# stripdriver.net
KiCad netlist of a schematic drawn in EasyEDA Pro
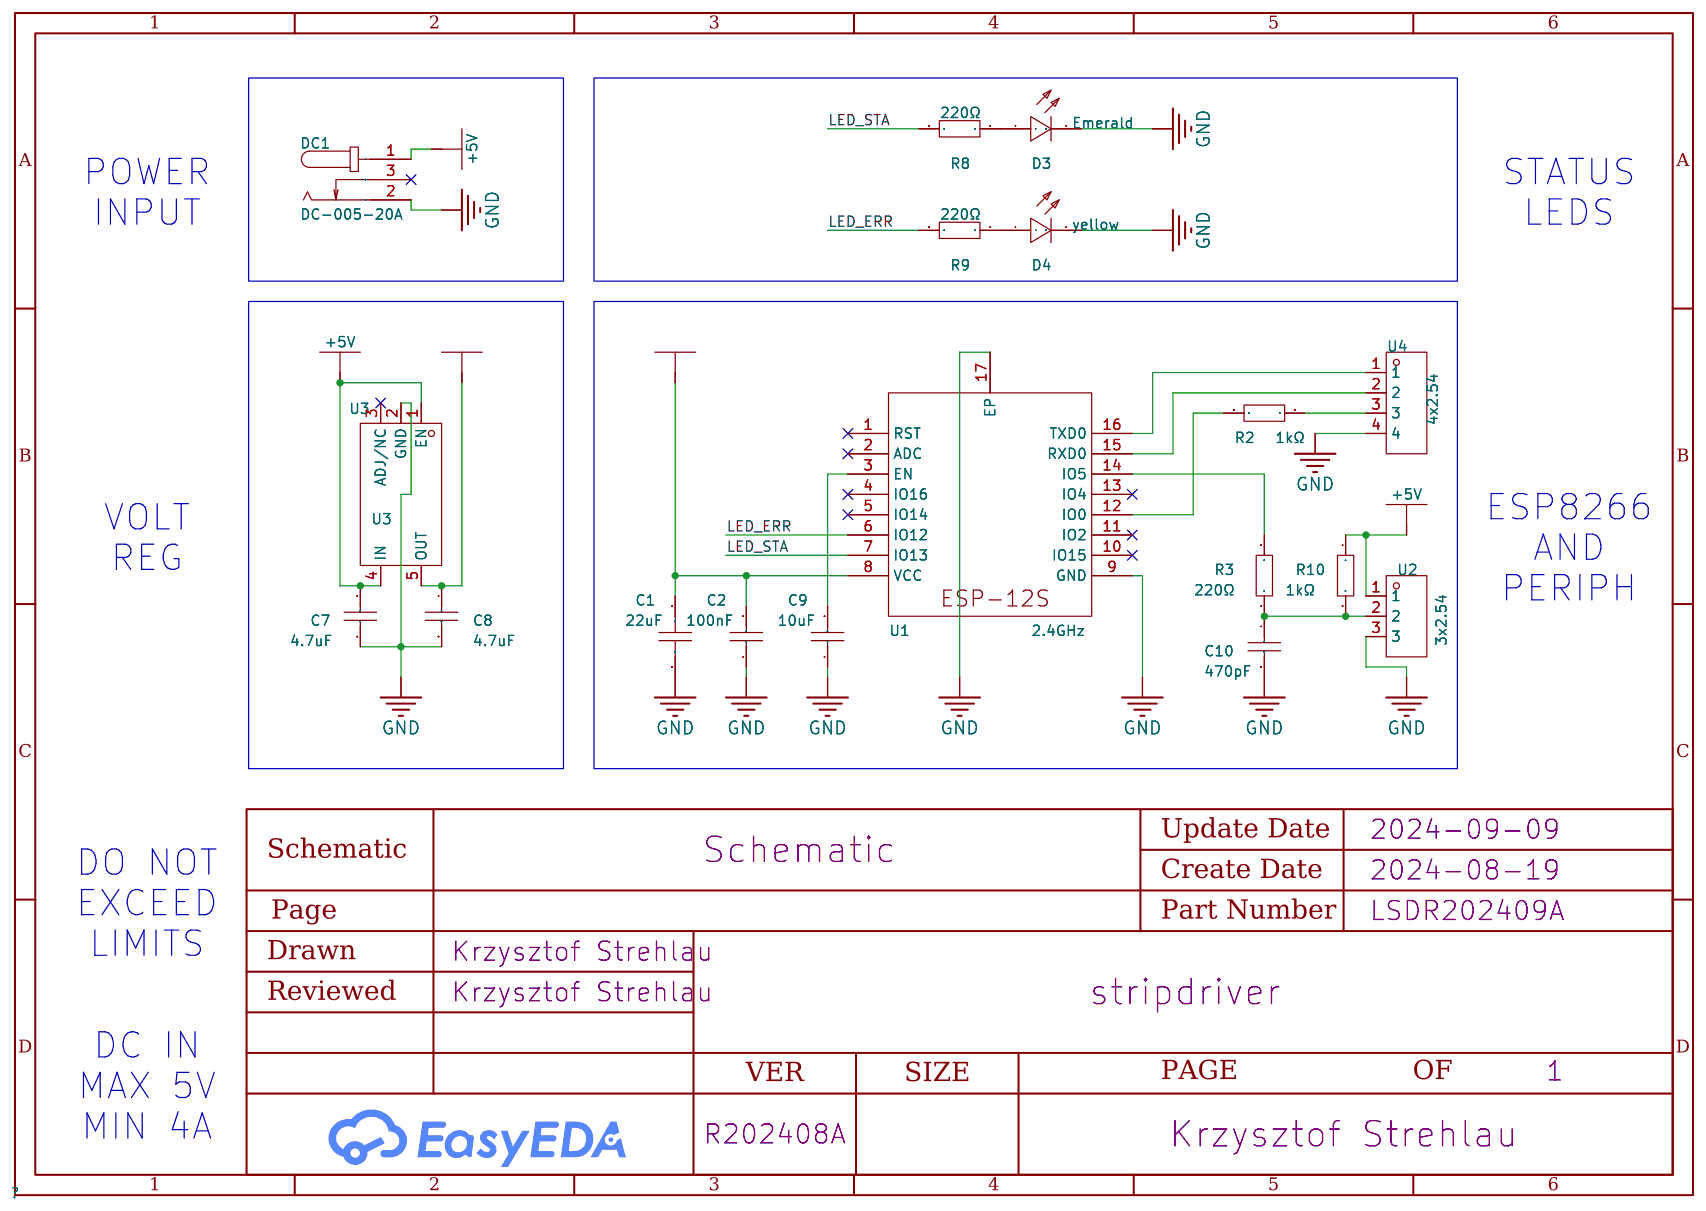
[diagram p0: schematic sheet]

(export (version "E")
  (design (tool "Eeschema 10.0.6"))
  (components
    (comp (ref "C1")
      (value "22uF")
      (footprint "easyedapro:C0805")
      (fields
        (field (name "Manufacturer Part") "CL21A226MAQNNNE")
        (field (name "Manufacturer") "SAMSUNG(三星)")
      )
      (libsource (lib "easyedapro") (part "CL21A226MAQNNNE"))
    )
    (comp (ref "C2")
      (value "100nF")
      (fields
        (field (name "Manufacturer Part") "CC0603KRX7R9BB104")
        (field (name "Manufacturer") "YAGEO(国巨)")
      )
      (libsource (lib "easyedapro") (part "cc0805krx7r9bb104"))
    )
    (comp (ref "C7")
      (value "4.7uF")
      (footprint "easyedapro:C0805")
      (fields
        (field (name "Manufacturer Part") "CL21A475KAQNNNE")
        (field (name "Manufacturer") "SAMSUNG(三星)")
      )
      (libsource (lib "easyedapro") (part "CL21A475KAQNNNE"))
    )
    (comp (ref "C8")
      (value "4.7uF")
      (footprint "easyedapro:C0805")
      (fields
        (field (name "Manufacturer Part") "CL21A475KAQNNNE")
        (field (name "Manufacturer") "SAMSUNG(三星)")
      )
      (libsource (lib "easyedapro") (part "CL21A475KAQNNNE"))
    )
    (comp (ref "C9")
      (value "10uF")
      (footprint "easyedapro:C0805")
      (fields
        (field (name "Manufacturer Part") "CL21A475KAQNNNE")
        (field (name "Manufacturer") "SAMSUNG(三星)")
      )
      (libsource (lib "easyedapro") (part "CL21A475KAQNNNE"))
    )
    (comp (ref "C10")
      (value "470pF")
      (fields
        (field (name "Manufacturer Part") "CC0603KRX7R9BB104")
        (field (name "Manufacturer") "YAGEO(国巨)")
      )
      (libsource (lib "easyedapro") (part "cc0805krx7r9bb104"))
    )
    (comp (ref "D3")
      (value "Emerald")
      (footprint "easyedapro:LED0603-R-RD")
      (fields
        (field (name "Manufacturer Part") "19-217/GHC-YR1S2/3T")
        (field (name "Manufacturer") "EVERLIGHT(亿光)")
      )
      (libsource (lib "easyedapro") (part "19-217/GHC-YR1S2/3T"))
    )
    (comp (ref "D4")
      (value "yellow")
      (footprint "easyedapro:LED0603-R-RD")
      (fields
        (field (name "Manufacturer Part") "19-213/Y2C-CQ2R2L/3T(CY)")
        (field (name "Manufacturer") "EVERLIGHT(亿光)")
      )
      (libsource (lib "easyedapro") (part "19-217/GHC-YR1S2/3T"))
    )
    (comp (ref "DC1")
      (value "DC-005-20A")
      (footprint "easyedapro:DC-IN-TH_DC005")
      (fields (field (name "Manufacturer") "韩国韩荣"))
      (libsource (lib "easyedapro") (part "DC-005-20A"))
    )
    (comp (ref "R2")
      (value "1kΩ")
      (fields (field (name "Manufacturer") "UNI-ROYAL(厚声)"))
      (libsource (lib "easyedapro") (part "0805w8f1052t5e"))
    )
    (comp (ref "R3")
      (value "220Ω")
      (fields (field (name "Manufacturer") "UNI-ROYAL(厚声)"))
      (libsource (lib "easyedapro") (part "0805w8f1052t5e"))
    )
    (comp (ref "R8")
      (value "220Ω")
      (footprint "easyedapro:R0603")
      (fields
        (field (name "Manufacturer Part") "0603WAF2200T5E")
        (field (name "Manufacturer") "UNI-ROYAL(厚声)")
      )
      (libsource (lib "easyedapro") (part "0603WAF2200T5E"))
    )
    (comp (ref "R9")
      (value "220Ω")
      (footprint "easyedapro:R0603")
      (fields
        (field (name "Manufacturer Part") "0603WAF2200T5E")
        (field (name "Manufacturer") "UNI-ROYAL(厚声)")
      )
      (libsource (lib "easyedapro") (part "0603WAF2200T5E"))
    )
    (comp (ref "R10")
      (value "1kΩ")
      (fields (field (name "Manufacturer") "UNI-ROYAL(厚声)"))
      (libsource (lib "easyedapro") (part "0805w8f1052t5e"))
    )
    (comp (ref "U1")
      (value "2.4GHz")
      (footprint "easyedapro:WIRELM-SMD_ESP-12S")
      (fields (field (name "Manufacturer Part") "ESP-12S") (field (name "Manufacturer") "Ai-Thinker(安信可)"))
      (libsource (lib "easyedapro") (part "ESP-12S"))
    )
    (comp (ref "U2")
      (value "3x2.54")
      (footprint "easyedapro:CONN-TH_DB125-2.54-3P-GN")
      (fields
        (field (name "Manufacturer Part") "DB125-2.54-3P-GN-S")
        (field (name "Manufacturer") "DIBO(地博电气)")
      )
      (libsource (lib "easyedapro") (part "DB125-2.54-3P-GN"))
    )
    (comp (ref "U3")
      (value "U3")
      (footprint "easyedapro:SOT-89-5_L4.5-W2.5-P1.50-LS4.5-BR")
      (fields (field (name "Manufacturer Part") "AP7361C-33Y5-13") (field (name "Manufacturer") "DIODES(美台)"))
      (libsource (lib "easyedapro") (part "AP7361C-33Y5-13"))
    )
    (comp (ref "U4")
      (value "4x2.54")
      (footprint "easyedapro:CONN-TH_DB125-2.54-4P-GN")
      (fields (field (name "Manufacturer") "DORABO(地博电气)"))
      (libsource (lib "easyedapro") (part "DB125-2.54-4P-GN"))
    )
  )
  (nets
    (net (code "1") (name "+3.3V") (class "Default")
      (node (ref "C1") (pin "1") (pinfunction "1_1") (pintype "input"))
      (node (ref "C2") (pin "2") (pinfunction "2_2") (pintype "input"))
      (node (ref "C8") (pin "1") (pinfunction "1_1") (pintype "input"))
      (node (ref "U1") (pin "8") (pinfunction "VCC_8") (pintype "unspecified"))
      (node (ref "U3") (pin "5") (pinfunction "OUT_5") (pintype "input"))
    )
    (net (code "2") (name "+5V") (class "Default")
      (node (ref "C7") (pin "1") (pinfunction "1_1") (pintype "input"))
      (node (ref "DC1") (pin "1") (pinfunction "1_1") (pintype "unspecified"))
      (node (ref "R10") (pin "1") (pinfunction "1_1") (pintype "input"))
      (node (ref "U2") (pin "1") (pinfunction "1_1") (pintype "input"))
      (node (ref "U3") (pin "1") (pinfunction "EN_1") (pintype "input"))
      (node (ref "U3") (pin "4") (pinfunction "IN_4") (pintype "input"))
    )
    (net (code "3") (name "/LED_ERR") (class "Default")
      (node (ref "R9") (pin "2") (pinfunction "2_2") (pintype "input"))
      (node (ref "U1") (pin "6") (pinfunction "IO12_6") (pintype "unspecified"))
    )
    (net (code "4") (name "/LED_STA") (class "Default")
      (node (ref "R8") (pin "2") (pinfunction "2_2") (pintype "input"))
      (node (ref "U1") (pin "7") (pinfunction "IO13_7") (pintype "unspecified"))
    )
    (net (code "5") (name "GND") (class "Default")
      (node (ref "C1") (pin "2") (pinfunction "2_2") (pintype "input"))
      (node (ref "C10") (pin "2") (pinfunction "2_2") (pintype "input"))
      (node (ref "C2") (pin "1") (pinfunction "1_1") (pintype "input"))
      (node (ref "C7") (pin "2") (pinfunction "2_2") (pintype "input"))
      (node (ref "C8") (pin "2") (pinfunction "2_2") (pintype "input"))
      (node (ref "C9") (pin "1") (pinfunction "1_1") (pintype "input"))
      (node (ref "D3") (pin "2") (pinfunction "C_2") (pintype "input"))
      (node (ref "D4") (pin "2") (pinfunction "C_2") (pintype "input"))
      (node (ref "DC1") (pin "2") (pinfunction "2_2") (pintype "unspecified"))
      (node (ref "U1") (pin "17") (pinfunction "EP_17") (pintype "unspecified"))
      (node (ref "U1") (pin "9") (pinfunction "GND_9") (pintype "unspecified"))
      (node (ref "U2") (pin "3") (pinfunction "3_3") (pintype "input"))
      (node (ref "U3") (pin "2") (pinfunction "GND_2") (pintype "input"))
      (node (ref "U4") (pin "4") (pinfunction "4_4") (pintype "unspecified"))
    )
    (net (code "6") (name "Net-(C10-Pad1)") (class "Default")
      (node (ref "C10") (pin "1") (pinfunction "1_1") (pintype "input"))
      (node (ref "R10") (pin "2") (pinfunction "2_2") (pintype "input"))
      (node (ref "R3") (pin "1") (pinfunction "1_1") (pintype "input"))
      (node (ref "U2") (pin "2") (pinfunction "2_2") (pintype "input"))
    )
    (net (code "7") (name "Net-(D3-A)") (class "Default")
      (node (ref "D3") (pin "1") (pinfunction "A_1") (pintype "input"))
      (node (ref "R8") (pin "1") (pinfunction "1_1") (pintype "input"))
    )
    (net (code "8") (name "Net-(D4-A)") (class "Default")
      (node (ref "D4") (pin "1") (pinfunction "A_1") (pintype "input"))
      (node (ref "R9") (pin "1") (pinfunction "1_1") (pintype "input"))
    )
    (net (code "9") (name "Net-(R2-Pad2)") (class "Default")
      (node (ref "R2") (pin "2") (pinfunction "2_2") (pintype "input"))
      (node (ref "U4") (pin "3") (pinfunction "3_3") (pintype "unspecified"))
    )
    (net (code "10") (name "Net-(U1-EN)") (class "Default")
      (node (ref "C9") (pin "2") (pinfunction "2_2") (pintype "input"))
      (node (ref "U1") (pin "3") (pinfunction "EN_3") (pintype "unspecified"))
    )
    (net (code "11") (name "Net-(U1-IO0)") (class "Default")
      (node (ref "R2") (pin "1") (pinfunction "1_1") (pintype "input"))
      (node (ref "U1") (pin "12") (pinfunction "IO0_12") (pintype "unspecified"))
    )
    (net (code "12") (name "Net-(U1-IO5)") (class "Default")
      (node (ref "R3") (pin "2") (pinfunction "2_2") (pintype "input"))
      (node (ref "U1") (pin "14") (pinfunction "IO5_14") (pintype "unspecified"))
    )
    (net (code "13") (name "Net-(U1-RXD0)") (class "Default")
      (node (ref "U1") (pin "15") (pinfunction "RXD0_15") (pintype "unspecified"))
      (node (ref "U4") (pin "2") (pinfunction "2_2") (pintype "unspecified"))
    )
    (net (code "14") (name "Net-(U1-TXD0)") (class "Default")
      (node (ref "U1") (pin "16") (pinfunction "TXD0_16") (pintype "unspecified"))
      (node (ref "U4") (pin "1") (pinfunction "1_1") (pintype "unspecified"))
    )
    (net (code "15") (name "unconnected-(DC1-Pad3)") (class "Default")
      (node (ref "DC1") (pin "3") (pinfunction "3_3") (pintype "unspecified+no_connect"))
    )
    (net (code "16") (name "unconnected-(U1-ADC-Pad2)") (class "Default")
      (node (ref "U1") (pin "2") (pinfunction "ADC_2") (pintype "unspecified+no_connect"))
    )
    (net (code "17") (name "unconnected-(U1-IO2-Pad11)") (class "Default")
      (node (ref "U1") (pin "11") (pinfunction "IO2_11") (pintype "unspecified+no_connect"))
    )
    (net (code "18") (name "unconnected-(U1-IO4-Pad13)") (class "Default")
      (node (ref "U1") (pin "13") (pinfunction "IO4_13") (pintype "unspecified+no_connect"))
    )
    (net (code "19") (name "unconnected-(U1-IO14-Pad5)") (class "Default")
      (node (ref "U1") (pin "5") (pinfunction "IO14_5") (pintype "unspecified+no_connect"))
    )
    (net (code "20") (name "unconnected-(U1-IO15-Pad10)") (class "Default")
      (node (ref "U1") (pin "10") (pinfunction "IO15_10") (pintype "unspecified+no_connect"))
    )
    (net (code "21") (name "unconnected-(U1-IO16-Pad4)") (class "Default")
      (node (ref "U1") (pin "4") (pinfunction "IO16_4") (pintype "unspecified+no_connect"))
    )
    (net (code "22") (name "unconnected-(U1-RST-Pad1)") (class "Default")
      (node (ref "U1") (pin "1") (pinfunction "RST_1") (pintype "unspecified+no_connect"))
    )
    (net (code "23") (name "unconnected-(U3-ADJ{slash}NC-Pad3)") (class "Default")
      (node (ref "U3") (pin "3") (pinfunction "ADJ/NC_3") (pintype "input+no_connect"))
    )
  )
)
